# 1.net
KiCad netlist of a schematic drawn in Altium Designer
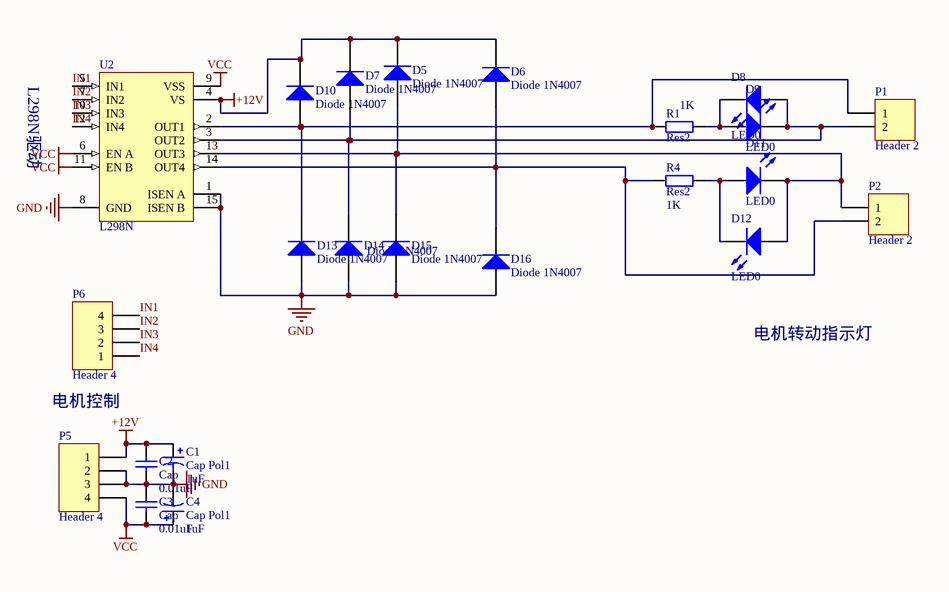
[diagram p0: 驱动电路1.SchDoc]

(export (version "E")
  (design (tool "Eeschema 10.0.6"))
  (components
    (comp (ref "C1")
      (value "Cap Pol1")
      (footprint "RB7.6-15")
      (description "Polarized Capacitor (Radial)")
      (fields (field (name "ALTIUM_VALUE") "1uF") (field (name "PUBLISHER") "Altium Limited"))
      (libsource (lib "Miscellaneous Devices") (part "Cap Pol1"))
    )
    (comp (ref "C2")
      (value "Cap")
      (footprint "RAD-0.3")
      (description "Capacitor")
      (fields (field (name "ALTIUM_VALUE") "0.01uF") (field (name "PUBLISHER") "Altium Limited"))
      (libsource (lib "Miscellaneous Devices") (part "Cap"))
    )
    (comp (ref "C3")
      (value "Cap")
      (footprint "RAD-0.3")
      (description "Capacitor")
      (fields (field (name "ALTIUM_VALUE") "0.01uF") (field (name "PUBLISHER") "Altium Limited"))
      (libsource (lib "Miscellaneous Devices") (part "Cap"))
    )
    (comp (ref "C4")
      (value "Cap Pol1")
      (footprint "RB7.6-15")
      (description "Polarized Capacitor (Radial)")
      (fields (field (name "ALTIUM_VALUE") "1uF") (field (name "PUBLISHER") "Altium Limited"))
      (libsource (lib "Miscellaneous Devices") (part "Cap Pol1"))
    )
    (comp (ref "D5")
      (value "Diode 1N4007")
      (footprint "DO-41")
      (description "1 Amp General Purpose Rectifier")
      (fields (field (name "PUBLISHER") "Altium Limited"))
      (libsource (lib "Miscellaneous Devices") (part "Diode 1N4007"))
    )
    (comp (ref "D6")
      (value "Diode 1N4007")
      (footprint "DO-41")
      (description "1 Amp General Purpose Rectifier")
      (fields (field (name "PUBLISHER") "Altium Limited"))
      (libsource (lib "Miscellaneous Devices") (part "Diode 1N4007"))
    )
    (comp (ref "D7")
      (value "Diode 1N4007")
      (footprint "DO-41")
      (description "1 Amp General Purpose Rectifier")
      (fields (field (name "PUBLISHER") "Altium Limited"))
      (libsource (lib "Miscellaneous Devices") (part "Diode 1N4007"))
    )
    (comp (ref "D8")
      (value "LED0")
      (footprint "LED-0")
      (description "Typical INFRARED GaAs LED")
      (fields (field (name "PUBLISHER") "Altium Limited"))
      (libsource (lib "Miscellaneous Devices") (part "LED0"))
    )
    (comp (ref "D9")
      (value "LED0")
      (footprint "LED-0")
      (description "Typical INFRARED GaAs LED")
      (fields (field (name "PUBLISHER") "Altium Limited"))
      (libsource (lib "Miscellaneous Devices") (part "LED0"))
    )
    (comp (ref "D10")
      (value "Diode 1N4007")
      (footprint "DO-41")
      (description "1 Amp General Purpose Rectifier")
      (fields (field (name "PUBLISHER") "Altium Limited"))
      (libsource (lib "Miscellaneous Devices") (part "Diode 1N4007"))
    )
    (comp (ref "D11")
      (value "LED0")
      (footprint "LED-0")
      (description "Typical INFRARED GaAs LED")
      (fields (field (name "PUBLISHER") "Altium Limited"))
      (libsource (lib "Miscellaneous Devices") (part "LED0"))
    )
    (comp (ref "D12")
      (value "LED0")
      (footprint "LED-0")
      (description "Typical INFRARED GaAs LED")
      (fields (field (name "PUBLISHER") "Altium Limited"))
      (libsource (lib "Miscellaneous Devices") (part "LED0"))
    )
    (comp (ref "D13")
      (value "Diode 1N4007")
      (footprint "DO-41")
      (description "1 Amp General Purpose Rectifier")
      (fields (field (name "PUBLISHER") "Altium Limited"))
      (libsource (lib "Miscellaneous Devices") (part "Diode 1N4007"))
    )
    (comp (ref "D14")
      (value "Diode 1N4007")
      (footprint "DO-41")
      (description "1 Amp General Purpose Rectifier")
      (fields (field (name "PUBLISHER") "Altium Limited"))
      (libsource (lib "Miscellaneous Devices") (part "Diode 1N4007"))
    )
    (comp (ref "D15")
      (value "Diode 1N4007")
      (footprint "DO-41")
      (description "1 Amp General Purpose Rectifier")
      (fields (field (name "PUBLISHER") "Altium Limited"))
      (libsource (lib "Miscellaneous Devices") (part "Diode 1N4007"))
    )
    (comp (ref "D16")
      (value "Diode 1N4007")
      (footprint "DO-41")
      (description "1 Amp General Purpose Rectifier")
      (fields (field (name "PUBLISHER") "Altium Limited"))
      (libsource (lib "Miscellaneous Devices") (part "Diode 1N4007"))
    )
    (comp (ref "P1")
      (value "Header 2")
      (footprint "HDR1X2")
      (description "Header, 2-Pin")
      (fields (field (name "PUBLISHER") "Altium Limited"))
      (libsource (lib "Miscellaneous Connectors") (part "Header 2"))
    )
    (comp (ref "P2")
      (value "Header 2")
      (footprint "HDR1X2")
      (description "Header, 2-Pin")
      (fields (field (name "PUBLISHER") "Altium Limited"))
      (libsource (lib "Miscellaneous Connectors") (part "Header 2"))
    )
    (comp (ref "P5")
      (value "Header 4")
      (footprint "HDR1X4")
      (description "Header, 4-Pin")
      (fields (field (name "PUBLISHER") "Altium Limited"))
      (libsource (lib "Miscellaneous Connectors") (part "Header 4"))
    )
    (comp (ref "P6")
      (value "Header 4")
      (footprint "HDR1X4")
      (description "Header, 4-Pin")
      (fields (field (name "PUBLISHER") "Altium Limited"))
      (libsource (lib "") (part "Header 4_1"))
    )
    (comp (ref "R1")
      (value "Res2")
      (footprint "AXIAL-0.4")
      (description "Resistor")
      (fields (field (name "ALTIUM_VALUE") "1K") (field (name "PUBLISHER") "Altium Limited"))
      (libsource (lib "Miscellaneous Devices") (part "Res2"))
    )
    (comp (ref "R4")
      (value "Res2")
      (footprint "AXIAL-0.4")
      (description "Resistor")
      (fields (field (name "ALTIUM_VALUE") "1K") (field (name "PUBLISHER") "Altium Limited"))
      (libsource (lib "Miscellaneous Devices") (part "Res2"))
    )
    (comp (ref "U2")
      (value "L298N")
      (footprint "Multiwatt15V")
      (description "Dual Full Bridge Driver")
      (fields (field (name "PUBLISHER") "Altium Limited"))
      (libsource (lib "ST Interface DC Motor Controller") (part "L298N"))
    )
  )
  (nets
    (net (code "1") (name "+12V") (class "Default")
      (node (ref "C1") (pin "1") (pinfunction "1_1") (pintype "passive"))
      (node (ref "C2") (pin "2") (pinfunction "2_2") (pintype "passive"))
      (node (ref "D10") (pin "2") (pinfunction "K_2") (pintype "passive"))
      (node (ref "D5") (pin "2") (pinfunction "K_2") (pintype "passive"))
      (node (ref "D6") (pin "2") (pinfunction "K_2") (pintype "passive"))
      (node (ref "D7") (pin "2") (pinfunction "K_2") (pintype "passive"))
      (node (ref "P5") (pin "1") (pinfunction "1_1") (pintype "passive"))
      (node (ref "U2") (pin "4") (pinfunction "VS_4") (pintype "power_in"))
    )
    (net (code "2") (name "/IN1") (class "Default")
      (node (ref "P6") (pin "4") (pinfunction "4_4") (pintype "passive"))
      (node (ref "U2") (pin "5") (pinfunction "IN1_5") (pintype "input"))
    )
    (net (code "3") (name "/IN2") (class "Default")
      (node (ref "P6") (pin "3") (pinfunction "3_3") (pintype "passive"))
      (node (ref "U2") (pin "7") (pinfunction "IN2_7") (pintype "input"))
    )
    (net (code "4") (name "/IN3") (class "Default")
      (node (ref "P6") (pin "2") (pinfunction "2_2") (pintype "passive"))
      (node (ref "U2") (pin "10") (pinfunction "IN3_10") (pintype "input"))
    )
    (net (code "5") (name "/IN4") (class "Default")
      (node (ref "P6") (pin "1") (pinfunction "1_1") (pintype "passive"))
      (node (ref "U2") (pin "12") (pinfunction "IN4_12") (pintype "input"))
    )
    (net (code "6") (name "GND") (class "Default")
      (node (ref "C1") (pin "2") (pinfunction "2_2") (pintype "passive"))
      (node (ref "C2") (pin "1") (pinfunction "1_1") (pintype "passive"))
      (node (ref "C3") (pin "2") (pinfunction "2_2") (pintype "passive"))
      (node (ref "C4") (pin "2") (pinfunction "2_2") (pintype "passive"))
      (node (ref "D13") (pin "1") (pinfunction "A_1") (pintype "passive"))
      (node (ref "D14") (pin "1") (pinfunction "A_1") (pintype "passive"))
      (node (ref "D15") (pin "1") (pinfunction "A_1") (pintype "passive"))
      (node (ref "D16") (pin "1") (pinfunction "A_1") (pintype "passive"))
      (node (ref "P5") (pin "2") (pinfunction "2_2") (pintype "passive"))
      (node (ref "P5") (pin "3") (pinfunction "3_3") (pintype "passive"))
      (node (ref "U2") (pin "1") (pinfunction "ISEN_A_1") (pintype "passive"))
      (node (ref "U2") (pin "15") (pinfunction "ISEN_B_15") (pintype "passive"))
      (node (ref "U2") (pin "8") (pinfunction "GND_8") (pintype "power_in"))
    )
    (net (code "7") (name "Net-(D8-K)") (class "Default")
      (node (ref "D8") (pin "2") (pinfunction "K_2") (pintype "passive"))
      (node (ref "D9") (pin "1") (pinfunction "A_1") (pintype "passive"))
      (node (ref "R1") (pin "2") (pinfunction "2_2") (pintype "passive"))
    )
    (net (code "8") (name "Net-(D10-A)") (class "Default")
      (node (ref "D10") (pin "1") (pinfunction "A_1") (pintype "passive"))
      (node (ref "D13") (pin "2") (pinfunction "K_2") (pintype "passive"))
      (node (ref "P1") (pin "1") (pinfunction "1_1") (pintype "passive"))
      (node (ref "R1") (pin "1") (pinfunction "1_1") (pintype "passive"))
      (node (ref "U2") (pin "2") (pinfunction "OUT1_2") (pintype "output"))
    )
    (net (code "9") (name "Net-(D11-A)") (class "Default")
      (node (ref "D11") (pin "1") (pinfunction "A_1") (pintype "passive"))
      (node (ref "D12") (pin "2") (pinfunction "K_2") (pintype "passive"))
      (node (ref "R4") (pin "2") (pinfunction "2_2") (pintype "passive"))
    )
    (net (code "10") (name "Net-(D11-K)") (class "Default")
      (node (ref "D11") (pin "2") (pinfunction "K_2") (pintype "passive"))
      (node (ref "D12") (pin "1") (pinfunction "A_1") (pintype "passive"))
      (node (ref "D15") (pin "2") (pinfunction "K_2") (pintype "passive"))
      (node (ref "D5") (pin "1") (pinfunction "A_1") (pintype "passive"))
      (node (ref "P2") (pin "1") (pinfunction "1_1") (pintype "passive"))
      (node (ref "U2") (pin "13") (pinfunction "OUT3_13") (pintype "output"))
    )
    (net (code "11") (name "Net-(D14-K)") (class "Default")
      (node (ref "D14") (pin "2") (pinfunction "K_2") (pintype "passive"))
      (node (ref "D7") (pin "1") (pinfunction "A_1") (pintype "passive"))
      (node (ref "D8") (pin "1") (pinfunction "A_1") (pintype "passive"))
      (node (ref "D9") (pin "2") (pinfunction "K_2") (pintype "passive"))
      (node (ref "P1") (pin "2") (pinfunction "2_2") (pintype "passive"))
      (node (ref "U2") (pin "3") (pinfunction "OUT2_3") (pintype "output"))
    )
    (net (code "12") (name "Net-(D16-K)") (class "Default")
      (node (ref "D16") (pin "2") (pinfunction "K_2") (pintype "passive"))
      (node (ref "D6") (pin "1") (pinfunction "A_1") (pintype "passive"))
      (node (ref "P2") (pin "2") (pinfunction "2_2") (pintype "passive"))
      (node (ref "R4") (pin "1") (pinfunction "1_1") (pintype "passive"))
      (node (ref "U2") (pin "14") (pinfunction "OUT4_14") (pintype "output"))
    )
    (net (code "13") (name "VCC") (class "Default")
      (node (ref "C3") (pin "1") (pinfunction "1_1") (pintype "passive"))
      (node (ref "C4") (pin "1") (pinfunction "1_1") (pintype "passive"))
      (node (ref "P5") (pin "4") (pinfunction "4_4") (pintype "passive"))
      (node (ref "U2") (pin "11") (pinfunction "EN_B_11") (pintype "input"))
      (node (ref "U2") (pin "6") (pinfunction "EN_A_6") (pintype "input"))
      (node (ref "U2") (pin "9") (pinfunction "VSS_9") (pintype "power_in"))
    )
  )
)
